# 02_MCU_LCD.net
KiCad netlist of a schematic drawn in Altium Designer
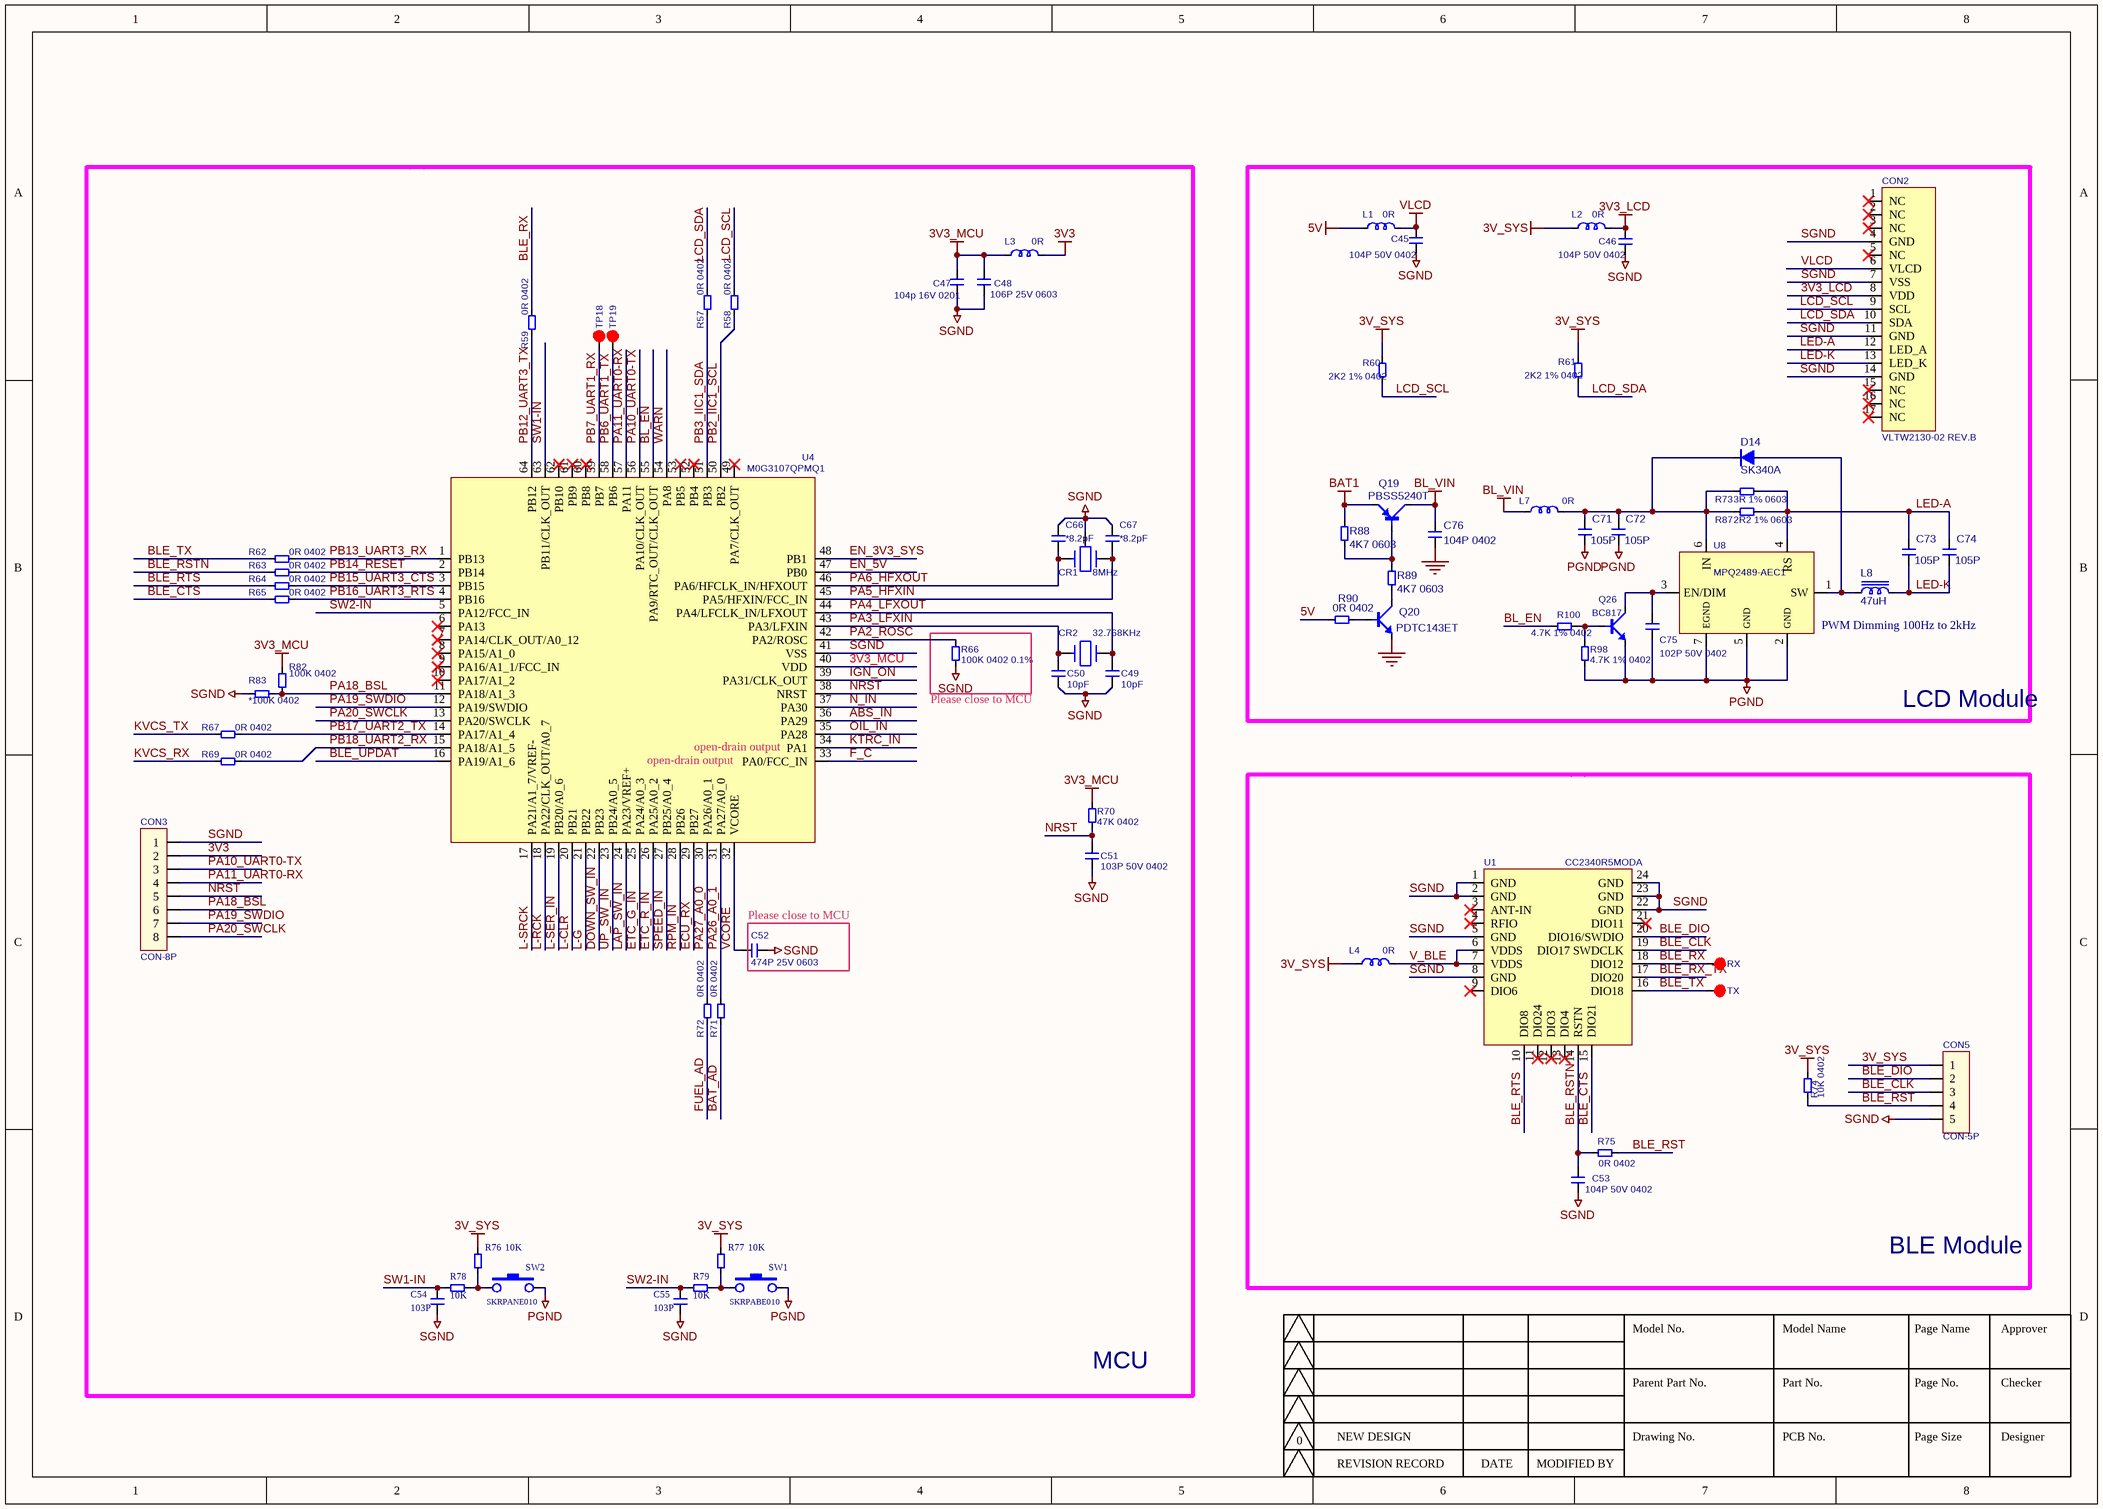
[diagram p0: 02_MCU_LCD.SchDoc]

(export (version "E")
  (design (tool "Eeschema 10.0.6"))
  (components
    (comp (ref "C45")
      (value "104P 50V 0402")
      (footprint "C0402")
      (description "Capacitor")
      (libsource (lib "CTE") (part "C"))
    )
    (comp (ref "C46")
      (value "104P 50V 0402")
      (footprint "C0402")
      (description "Capacitor")
      (libsource (lib "CTE") (part "C"))
    )
    (comp (ref "C47")
      (value "104p 16V 0201")
      (footprint "C0201")
      (description "Capacitor")
      (libsource (lib "CTE") (part "C"))
    )
    (comp (ref "C48")
      (value "106P 25V 0603")
      (footprint "C0603")
      (description "Capacitor")
      (libsource (lib "CTE") (part "C"))
    )
    (comp (ref "C49")
      (value "10pF")
      (footprint "C0402")
      (description "Capacitor")
      (libsource (lib "CTE") (part "C"))
    )
    (comp (ref "C50")
      (value "10pF")
      (footprint "C0402")
      (description "Capacitor")
      (libsource (lib "CTE") (part "C"))
    )
    (comp (ref "C51")
      (value "103P 50V 0402")
      (footprint "C0402")
      (description "Capacitor")
      (libsource (lib "CTE") (part "C"))
    )
    (comp (ref "C52")
      (value "474P 25V 0603")
      (footprint "C0603")
      (description "Capacitor")
      (libsource (lib "CTE") (part "C"))
    )
    (comp (ref "C53")
      (value "104P 50V 0402")
      (footprint "C0402")
      (description "Capacitor")
      (libsource (lib "CTE") (part "C"))
    )
    (comp (ref "C54")
      (value "103P")
      (footprint "C0402")
      (description "Capacitor")
      (libsource (lib "CTE") (part "C"))
    )
    (comp (ref "C55")
      (value "103P")
      (footprint "C0402")
      (description "Capacitor")
      (libsource (lib "CTE") (part "C"))
    )
    (comp (ref "C66")
      (value "*8.2pF")
      (footprint "C0402")
      (description "Capacitor")
      (libsource (lib "CTE") (part "C"))
    )
    (comp (ref "C67")
      (value "*8.2pF")
      (footprint "C0402")
      (description "Capacitor")
      (libsource (lib "CTE") (part "C"))
    )
    (comp (ref "C71")
      (value "105P")
      (footprint "C0603")
      (description "Capacitor")
      (libsource (lib "CTE") (part "C"))
    )
    (comp (ref "C72")
      (value "105P")
      (footprint "C0603")
      (description "Capacitor")
      (libsource (lib "CTE") (part "C"))
    )
    (comp (ref "C73")
      (value "105P")
      (footprint "C0603")
      (description "Capacitor")
      (libsource (lib "CTE") (part "C"))
    )
    (comp (ref "C74")
      (value "105P")
      (footprint "C0603")
      (description "Capacitor")
      (libsource (lib "CTE") (part "C"))
    )
    (comp (ref "C75")
      (value "102P 50V 0402")
      (footprint "C0402")
      (description "Capacitor")
      (libsource (lib "CTE") (part "C"))
    )
    (comp (ref "C76")
      (value "104P 0402")
      (footprint "c0402")
      (description "Capacitor")
      (libsource (lib "CTE") (part "C"))
    )
    (comp (ref "CON2")
      (value "VLTW2130-02 REV.B")
      (footprint "FPC-BL112-17P")
      (libsource (lib "Schlib1") (part "VLTW2130-02 REV.B"))
    )
    (comp (ref "CON3")
      (value "CON-8P")
      (footprint "CON-2.0(9021-N)-8P")
      (libsource (lib "CTE") (part "CON-8P"))
    )
    (comp (ref "CON5") (value "CON-5P") (footprint "CON-2.0V-5P") (libsource (lib "CTE") (part "CON-5P")))
    (comp (ref "CR1")
      (value "8MHz")
      (footprint "CR-3CE")
      (description "Crystal")
      (libsource (lib "CTE") (part "CR-1"))
    )
    (comp (ref "CR2")
      (value "32.768KHz")
      (footprint "CR-FC-13A")
      (description "Crystal")
      (libsource (lib "CTE") (part "CR-2"))
    )
    (comp (ref "D14")
      (value "SK340A")
      (footprint "D-SMA")
      (description "BAS16/RR264/1N4148/FM4004/SS14/SSL14/V15PL50")
      (libsource (lib "*") (part "D-SMD"))
    )
    (comp (ref "L1")
      (value "0R")
      (footprint "0603")
      (description "BEAD101")
      (libsource (lib "CTE") (part "L"))
    )
    (comp (ref "L2")
      (value "0R")
      (footprint "0603")
      (description "BEAD101")
      (libsource (lib "CTE") (part "L"))
    )
    (comp (ref "L3")
      (value "0R")
      (footprint "0603")
      (description "BEAD101")
      (libsource (lib "CTE") (part "L"))
    )
    (comp (ref "L4")
      (value "0R")
      (footprint "0603")
      (description "BEAD101")
      (libsource (lib "CTE") (part "L"))
    )
    (comp (ref "L7")
      (value "0R")
      (footprint "0603")
      (description "BEAD101")
      (libsource (lib "CTE") (part "L"))
    )
    (comp (ref "L8") (value "47uH") (footprint "L-7.4X6.8") (libsource (lib "*") (part "L-1")))
    (comp (ref "Q19")
      (value "PBSS5240T")
      (footprint "SOT23-RF")
      (description "BC807，2SA1812，PBSS9110T")
      (libsource (lib "CTE") (part "Q-PNP(BCE)"))
    )
    (comp (ref "Q20")
      (value "PDTC143ET")
      (footprint "SOT23-RF")
      (description "BC817，PDTC143ET，2SD2211，2SD1918")
      (libsource (lib "CTE") (part "Q-NPN(BCE)"))
    )
    (comp (ref "Q26")
      (value "BC817")
      (footprint "SOT323")
      (description "BC817，PDTC143ET，2SD2211，2SD1918")
      (libsource (lib "CTE") (part "Q-NPN(BCE)"))
    )
    (comp (ref "R57") (value "0R 0402") (footprint "0402") (libsource (lib "CTE") (part "R")))
    (comp (ref "R58") (value "0R 0402") (footprint "0402") (libsource (lib "CTE") (part "R")))
    (comp (ref "R59") (value "0R 0402") (footprint "0402") (libsource (lib "CTE") (part "R")))
    (comp (ref "R60") (value "2K2 1% 0402") (footprint "0402") (libsource (lib "CTE") (part "R")))
    (comp (ref "R61") (value "2K2 1% 0402") (footprint "0402") (libsource (lib "CTE") (part "R")))
    (comp (ref "R62") (value "0R 0402") (footprint "0402") (libsource (lib "CTE") (part "R")))
    (comp (ref "R63")
      (value "0R 0402")
      (footprint "0402")
      (description "0603")
      (libsource (lib "PADS") (part "R-0603"))
    )
    (comp (ref "R64") (value "0R 0402") (footprint "0402") (libsource (lib "CTE") (part "R")))
    (comp (ref "R65") (value "0R 0402") (footprint "0402") (libsource (lib "CTE") (part "R")))
    (comp (ref "R66")
      (value "100K 0402 0.1%")
      (footprint "0402")
      (description "0603")
      (libsource (lib "PADS") (part "R-0603"))
    )
    (comp (ref "R67") (value "0R 0402") (footprint "0402") (libsource (lib "CTE") (part "R")))
    (comp (ref "R69") (value "0R 0402") (footprint "0402") (libsource (lib "CTE") (part "R")))
    (comp (ref "R70")
      (value "47K 0402")
      (footprint "0402")
      (description "0603")
      (libsource (lib "PADS") (part "R-0603"))
    )
    (comp (ref "R71") (value "0R 0402") (footprint "0402") (libsource (lib "CTE") (part "R")))
    (comp (ref "R72") (value "0R 0402") (footprint "0402") (libsource (lib "CTE") (part "R")))
    (comp (ref "R73") (value "3R 1% 0603") (footprint "0603") (libsource (lib "CTE") (part "R")))
    (comp (ref "R74")
      (value "10K 0402")
      (footprint "0402")
      (description "0603")
      (libsource (lib "PADS") (part "R-0603"))
    )
    (comp (ref "R75")
      (value "0R 0402")
      (footprint "0402")
      (description "0603")
      (libsource (lib "PADS") (part "R-0603"))
    )
    (comp (ref "R76")
      (value "10K")
      (footprint "0402")
      (description "0603")
      (libsource (lib "CTE") (part "R-0603"))
    )
    (comp (ref "R77")
      (value "10K")
      (footprint "0402")
      (description "0603")
      (libsource (lib "CTE") (part "R-0603"))
    )
    (comp (ref "R78")
      (value "10K")
      (footprint "0402")
      (description "0603")
      (libsource (lib "CTE") (part "R-0603"))
    )
    (comp (ref "R79")
      (value "10K")
      (footprint "0402")
      (description "0603")
      (libsource (lib "CTE") (part "R-0603"))
    )
    (comp (ref "R82")
      (value "100K 0402")
      (footprint "0402")
      (description "0603")
      (libsource (lib "PADS") (part "R-0603"))
    )
    (comp (ref "R83")
      (value "*100K 0402")
      (footprint "0402")
      (description "0603")
      (libsource (lib "PADS") (part "R-0603"))
    )
    (comp (ref "R87") (value "2R2 1% 0603") (footprint "0603") (libsource (lib "CTE") (part "R")))
    (comp (ref "R88") (value "4K7 0603") (footprint "0603") (libsource (lib "CTE") (part "R")))
    (comp (ref "R89") (value "4K7 0603") (footprint "0603") (libsource (lib "CTE") (part "R")))
    (comp (ref "R90")
      (value "0R 0402")
      (footprint "0402")
      (description "0603")
      (libsource (lib "PADS") (part "R-0603"))
    )
    (comp (ref "R98") (value "4.7K 1% 0402") (footprint "0402") (libsource (lib "CTE") (part "R")))
    (comp (ref "R100") (value "4.7K 1% 0402") (footprint "0402") (libsource (lib "CTE") (part "R")))
    (comp (ref "RX") (value "TEST") (footprint "TEST") (libsource (lib "CTE") (part "TEST")))
    (comp (ref "SW1") (value "SKRPABE010") (footprint "SW-SKRPABE010") (libsource (lib "CTE") (part "SW-PB")))
    (comp (ref "SW2") (value "SKRPANE010") (footprint "SW-SKRPABE010") (libsource (lib "CTE") (part "SW-PB")))
    (comp (ref "TP18") (value "TEST") (footprint "TEST") (libsource (lib "CTE") (part "TEST")))
    (comp (ref "TP19") (value "TEST") (footprint "TEST") (libsource (lib "CTE") (part "TEST")))
    (comp (ref "TX") (value "TEST") (footprint "TEST") (libsource (lib "CTE") (part "TEST")))
    (comp (ref "U1")
      (value "CC2340R5MODA")
      (footprint "IC-MOD-CC2340R5")
      (libsource (lib "Schlib1") (part "CC234055MODA"))
    )
    (comp (ref "U4")
      (value "M0G3107QPMQ1")
      (footprint "IC-M0G3107-64")
      (libsource (lib "Schlib1") (part "M0G3107QPMQ1"))
    )
    (comp (ref "U8")
      (value "MPQ2489-AEC1")
      (footprint "IC-QFN6-3X3")
      (libsource (lib "Schlib1") (part "MPQ2489-AEC1"))
    )
  )
  (nets
    (net (code "1") (name "/ABS_IN") (class "Default")
      (node (ref "U4") (pin "36") (pinfunction "PA29_36") (pintype "passive"))
    )
    (net (code "2") (name "/BAT_AD") (class "Default")
      (node (ref "R71") (pin "2") (pinfunction "2_2") (pintype "passive"))
    )
    (net (code "3") (name "/BLE_CLK") (class "Default")
      (node (ref "CON5") (pin "3") (pinfunction "3_3") (pintype "passive"))
      (node (ref "U1") (pin "19") (pinfunction "DIO17_SWDCLK_19") (pintype "passive"))
    )
    (net (code "4") (name "/BLE_CTS") (class "Default")
      (node (ref "R65") (pin "2") (pinfunction "2_2") (pintype "passive"))
      (node (ref "U1") (pin "15") (pinfunction "DIO21_15") (pintype "passive"))
    )
    (net (code "5") (name "/BLE_DIO") (class "Default")
      (node (ref "CON5") (pin "2") (pinfunction "2_2") (pintype "passive"))
      (node (ref "U1") (pin "20") (pinfunction "DIO16/SWDIO_20") (pintype "passive"))
    )
    (net (code "6") (name "/BLE_RST") (class "Default")
      (node (ref "CON5") (pin "4") (pinfunction "4_4") (pintype "passive"))
      (node (ref "R74") (pin "1") (pinfunction "1_1") (pintype "passive"))
      (node (ref "R75") (pin "2") (pinfunction "2_2") (pintype "passive"))
    )
    (net (code "7") (name "/BLE_RSTN") (class "Default")
      (node (ref "C53") (pin "1") (pinfunction "1_1") (pintype "passive"))
      (node (ref "R63") (pin "1") (pinfunction "1_1") (pintype "passive"))
      (node (ref "R75") (pin "1") (pinfunction "1_1") (pintype "passive"))
      (node (ref "U1") (pin "14") (pinfunction "RSTN_14") (pintype "passive"))
    )
    (net (code "8") (name "/BLE_RTS") (class "Default")
      (node (ref "R64") (pin "2") (pinfunction "2_2") (pintype "passive"))
      (node (ref "U1") (pin "10") (pinfunction "DIO8_10") (pintype "passive"))
    )
    (net (code "9") (name "/BLE_RX") (class "Default")
      (node (ref "R59") (pin "1") (pinfunction "1_1") (pintype "passive"))
      (node (ref "RX") (pin "TP") (pinfunction "TP_TP") (pintype "passive"))
      (node (ref "U1") (pin "18") (pinfunction "DIO12_18") (pintype "passive"))
    )
    (net (code "10") (name "/BLE_RX_TX") (class "Default")
      (node (ref "U1") (pin "17") (pinfunction "DIO20_17") (pintype "passive"))
    )
    (net (code "11") (name "/BLE_TX") (class "Default")
      (node (ref "R62") (pin "2") (pinfunction "2_2") (pintype "passive"))
      (node (ref "TX") (pin "TP") (pinfunction "TP_TP") (pintype "passive"))
      (node (ref "U1") (pin "16") (pinfunction "DIO18_16") (pintype "passive"))
    )
    (net (code "12") (name "/BLE_UPDAT") (class "Default")
      (node (ref "U4") (pin "16") (pinfunction "PA19/A1_6_16") (pintype "passive"))
    )
    (net (code "13") (name "/BL_EN") (class "Default")
      (node (ref "R100") (pin "2") (pinfunction "2_2") (pintype "passive"))
      (node (ref "U4") (pin "55") (pinfunction "PA9/RTC_OUT/CLK_OUT_55") (pintype "passive"))
    )
    (net (code "14") (name "/DOWN_SW_IN") (class "Default")
      (node (ref "U4") (pin "22") (pinfunction "PB23_22") (pintype "passive"))
    )
    (net (code "15") (name "/ECU_RX") (class "Default")
      (node (ref "U4") (pin "29") (pinfunction "PB27_29") (pintype "passive"))
    )
    (net (code "16") (name "/EN_3V3_SYS") (class "Default")
      (node (ref "U4") (pin "48") (pinfunction "PB1_48") (pintype "passive"))
    )
    (net (code "17") (name "/EN_5V") (class "Default")
      (node (ref "U4") (pin "47") (pinfunction "PB0_47") (pintype "passive"))
    )
    (net (code "18") (name "/ETC_G_IN") (class "Default")
      (node (ref "U4") (pin "25") (pinfunction "PA24/A0_3_25") (pintype "passive"))
    )
    (net (code "19") (name "/ETC_R_IN") (class "Default")
      (node (ref "U4") (pin "26") (pinfunction "PA25/A0_2_26") (pintype "passive"))
    )
    (net (code "20") (name "/FUEL_AD") (class "Default")
      (node (ref "R72") (pin "2") (pinfunction "2_2") (pintype "passive"))
    )
    (net (code "21") (name "/F_C") (class "Default")
      (node (ref "U4") (pin "33") (pinfunction "PA0/FCC_IN_33") (pintype "passive"))
    )
    (net (code "22") (name "/IGN_ON") (class "Default")
      (node (ref "U4") (pin "39") (pinfunction "PA31/CLK_OUT_39") (pintype "passive"))
    )
    (net (code "23") (name "/KTRC_IN") (class "Default")
      (node (ref "U4") (pin "34") (pinfunction "PA1_34") (pintype "passive"))
    )
    (net (code "24") (name "/KVCS_RX") (class "Default")
      (node (ref "R69") (pin "1") (pinfunction "1_1") (pintype "passive"))
    )
    (net (code "25") (name "/KVCS_TX") (class "Default")
      (node (ref "R67") (pin "1") (pinfunction "1_1") (pintype "passive"))
    )
    (net (code "26") (name "/L-CLR") (class "Default")
      (node (ref "U4") (pin "20") (pinfunction "PB21_20") (pintype "passive"))
    )
    (net (code "27") (name "/L-G") (class "Default")
      (node (ref "U4") (pin "21") (pinfunction "PB22_21") (pintype "passive"))
    )
    (net (code "28") (name "/L-RCK") (class "Default")
      (node (ref "U4") (pin "18") (pinfunction "PA22/CLK_OUT/A0_7_18") (pintype "passive"))
    )
    (net (code "29") (name "/L-SER_IN") (class "Default")
      (node (ref "U4") (pin "19") (pinfunction "PB20/A0_6_19") (pintype "passive"))
    )
    (net (code "30") (name "/L-SRCK") (class "Default")
      (node (ref "U4") (pin "17") (pinfunction "PA21/A1_7/VREF-_17") (pintype "passive"))
    )
    (net (code "31") (name "/LAP_SW_IN") (class "Default")
      (node (ref "U4") (pin "24") (pinfunction "PA23/VREF+_24") (pintype "passive"))
    )
    (net (code "32") (name "/LCD_SCL") (class "Default")
      (node (ref "CON2") (pin "9") (pinfunction "SCL_9") (pintype "passive"))
      (node (ref "R58") (pin "2") (pinfunction "2_2") (pintype "passive"))
      (node (ref "R60") (pin "1") (pinfunction "1_1") (pintype "passive"))
    )
    (net (code "33") (name "/LCD_SDA") (class "Default")
      (node (ref "CON2") (pin "10") (pinfunction "SDA_10") (pintype "passive"))
      (node (ref "R57") (pin "2") (pinfunction "2_2") (pintype "passive"))
      (node (ref "R61") (pin "1") (pinfunction "1_1") (pintype "passive"))
    )
    (net (code "34") (name "/LED-A") (class "Default")
      (node (ref "C73") (pin "1") (pinfunction "1_1") (pintype "passive"))
      (node (ref "C74") (pin "1") (pinfunction "1_1") (pintype "passive"))
      (node (ref "CON2") (pin "12") (pinfunction "LED_A_12") (pintype "passive"))
      (node (ref "R73") (pin "1") (pinfunction "1_1") (pintype "passive"))
      (node (ref "R87") (pin "1") (pinfunction "1_1") (pintype "passive"))
      (node (ref "U8") (pin "4") (pinfunction "RS_4") (pintype "passive"))
    )
    (net (code "35") (name "/LED-K") (class "Default")
      (node (ref "C73") (pin "2") (pinfunction "2_2") (pintype "passive"))
      (node (ref "C74") (pin "2") (pinfunction "2_2") (pintype "passive"))
      (node (ref "CON2") (pin "13") (pinfunction "LED_K_13") (pintype "passive"))
      (node (ref "L8") (pin "2") (pinfunction "2_2") (pintype "passive"))
    )
    (net (code "36") (name "/NRST") (class "Default")
      (node (ref "C51") (pin "1") (pinfunction "1_1") (pintype "passive"))
      (node (ref "CON3") (pin "5") (pinfunction "5_5") (pintype "passive"))
      (node (ref "R70") (pin "2") (pinfunction "2_2") (pintype "passive"))
      (node (ref "U4") (pin "38") (pinfunction "NRST_38") (pintype "passive"))
    )
    (net (code "37") (name "/N_IN") (class "Default")
      (node (ref "U4") (pin "37") (pinfunction "PA30_37") (pintype "passive"))
    )
    (net (code "38") (name "/OIL_IN") (class "Default")
      (node (ref "U4") (pin "35") (pinfunction "PA28_35") (pintype "passive"))
    )
    (net (code "39") (name "/PA2_ROSC") (class "Default")
      (node (ref "R66") (pin "1") (pinfunction "1_1") (pintype "passive"))
      (node (ref "U4") (pin "42") (pinfunction "PA2/ROSC_42") (pintype "passive"))
    )
    (net (code "40") (name "/PA3_LFXIN") (class "Default")
      (node (ref "C50") (pin "1") (pinfunction "1_1") (pintype "passive"))
      (node (ref "CR2") (pin "2") (pinfunction "2_2") (pintype "passive"))
      (node (ref "U4") (pin "43") (pinfunction "PA3/LFXIN_43") (pintype "passive"))
    )
    (net (code "41") (name "/PA4_LFXOUT") (class "Default")
      (node (ref "C49") (pin "1") (pinfunction "1_1") (pintype "passive"))
      (node (ref "CR2") (pin "1") (pinfunction "1_1") (pintype "passive"))
      (node (ref "U4") (pin "44") (pinfunction "PA4/LFCLK_IN/LFXOUT_44") (pintype "passive"))
    )
    (net (code "42") (name "/PA5_HFXIN") (class "Default")
      (node (ref "C67") (pin "1") (pinfunction "1_1") (pintype "passive"))
      (node (ref "CR1") (pin "2") (pinfunction "2_2") (pintype "passive"))
      (node (ref "U4") (pin "45") (pinfunction "PA5/HFXIN/FCC_IN_45") (pintype "passive"))
    )
    (net (code "43") (name "/PA6_HFXOUT") (class "Default")
      (node (ref "C66") (pin "1") (pinfunction "1_1") (pintype "passive"))
      (node (ref "CR1") (pin "1") (pinfunction "1_1") (pintype "passive"))
      (node (ref "U4") (pin "46") (pinfunction "PA6/HFCLK_IN/HFXOUT_46") (pintype "passive"))
    )
    (net (code "44") (name "/PA10_UART0-TX") (class "Default")
      (node (ref "CON3") (pin "3") (pinfunction "3_3") (pintype "passive"))
      (node (ref "U4") (pin "56") (pinfunction "PA10/CLK_OUT_56") (pintype "passive"))
    )
    (net (code "45") (name "/PA11_UART0-RX") (class "Default")
      (node (ref "CON3") (pin "4") (pinfunction "4_4") (pintype "passive"))
      (node (ref "U4") (pin "57") (pinfunction "PA11_57") (pintype "passive"))
    )
    (net (code "46") (name "/PA18_BSL") (class "Default")
      (node (ref "CON3") (pin "6") (pinfunction "6_6") (pintype "passive"))
      (node (ref "R82") (pin "2") (pinfunction "2_2") (pintype "passive"))
      (node (ref "R83") (pin "1") (pinfunction "1_1") (pintype "passive"))
      (node (ref "U4") (pin "11") (pinfunction "PA18/A1_3_11") (pintype "passive"))
    )
    (net (code "47") (name "/PA19_SWDIO") (class "Default")
      (node (ref "CON3") (pin "7") (pinfunction "7_7") (pintype "passive"))
      (node (ref "U4") (pin "12") (pinfunction "PA19/SWDIO_12") (pintype "passive"))
    )
    (net (code "48") (name "/PA20_SWCLK") (class "Default")
      (node (ref "CON3") (pin "8") (pinfunction "8_8") (pintype "passive"))
      (node (ref "U4") (pin "13") (pinfunction "PA20/SWCLK_13") (pintype "passive"))
    )
    (net (code "49") (name "/PA26_A0_1") (class "Default")
      (node (ref "R71") (pin "1") (pinfunction "1_1") (pintype "passive"))
      (node (ref "U4") (pin "31") (pinfunction "PA27/A0_0_31") (pintype "passive"))
    )
    (net (code "50") (name "/PA27_A0_0") (class "Default")
      (node (ref "R72") (pin "1") (pinfunction "1_1") (pintype "passive"))
      (node (ref "U4") (pin "30") (pinfunction "PA26/A0_1_30") (pintype "passive"))
    )
    (net (code "51") (name "/PB2_IIC1_SCL") (class "Default")
      (node (ref "R58") (pin "1") (pinfunction "1_1") (pintype "passive"))
      (node (ref "U4") (pin "50") (pinfunction "PB2_50") (pintype "passive"))
    )
    (net (code "52") (name "/PB3_IIC1_SDA") (class "Default")
      (node (ref "R57") (pin "1") (pinfunction "1_1") (pintype "passive"))
      (node (ref "U4") (pin "51") (pinfunction "PB3_51") (pintype "passive"))
    )
    (net (code "53") (name "/PB6_UART1_TX") (class "Default")
      (node (ref "TP19") (pin "TP") (pinfunction "TP_TP") (pintype "passive"))
      (node (ref "U4") (pin "58") (pinfunction "PB6_58") (pintype "passive"))
    )
    (net (code "54") (name "/PB7_UART1_RX") (class "Default")
      (node (ref "TP18") (pin "TP") (pinfunction "TP_TP") (pintype "passive"))
      (node (ref "U4") (pin "59") (pinfunction "PB7_59") (pintype "passive"))
    )
    (net (code "55") (name "/PB12_UART3_TX") (class "Default")
      (node (ref "R59") (pin "2") (pinfunction "2_2") (pintype "passive"))
      (node (ref "U4") (pin "64") (pinfunction "PB12_64") (pintype "passive"))
    )
    (net (code "56") (name "/PB13_UART3_RX") (class "Default")
      (node (ref "R62") (pin "1") (pinfunction "1_1") (pintype "passive"))
      (node (ref "U4") (pin "1") (pinfunction "PB13_1") (pintype "passive"))
    )
    (net (code "57") (name "/PB14_RESET") (class "Default")
      (node (ref "R63") (pin "2") (pinfunction "2_2") (pintype "passive"))
      (node (ref "U4") (pin "2") (pinfunction "PB14_2") (pintype "passive"))
    )
    (net (code "58") (name "/PB15_UART3_CTS") (class "Default")
      (node (ref "R64") (pin "1") (pinfunction "1_1") (pintype "passive"))
      (node (ref "U4") (pin "3") (pinfunction "PB15_3") (pintype "passive"))
    )
    (net (code "59") (name "/PB16_UART3_RTS") (class "Default")
      (node (ref "R65") (pin "1") (pinfunction "1_1") (pintype "passive"))
      (node (ref "U4") (pin "4") (pinfunction "PB16_4") (pintype "passive"))
    )
    (net (code "60") (name "/PB17_UART2_TX") (class "Default")
      (node (ref "R67") (pin "2") (pinfunction "2_2") (pintype "passive"))
      (node (ref "U4") (pin "14") (pinfunction "PA17/A1_4_14") (pintype "passive"))
    )
    (net (code "61") (name "/PB18_UART2_RX") (class "Default")
      (node (ref "R69") (pin "2") (pinfunction "2_2") (pintype "passive"))
      (node (ref "U4") (pin "15") (pinfunction "PA18/A1_5_15") (pintype "passive"))
    )
    (net (code "62") (name "/RPM_IN") (class "Default")
      (node (ref "U4") (pin "28") (pinfunction "PB26_28") (pintype "passive"))
    )
    (net (code "63") (name "/SPEED_IN") (class "Default")
      (node (ref "U4") (pin "27") (pinfunction "PB25/A0_4_27") (pintype "passive"))
    )
    (net (code "64") (name "/SW1-IN") (class "Default")
      (node (ref "C54") (pin "1") (pinfunction "1_1") (pintype "passive"))
      (node (ref "R78") (pin "2") (pinfunction "2_2") (pintype "passive"))
      (node (ref "U4") (pin "63") (pinfunction "PB11/CLK_OUT_63") (pintype "passive"))
    )
    (net (code "65") (name "/SW2-IN") (class "Default")
      (node (ref "C55") (pin "1") (pinfunction "1_1") (pintype "passive"))
      (node (ref "R79") (pin "2") (pinfunction "2_2") (pintype "passive"))
      (node (ref "U4") (pin "5") (pinfunction "PA12/FCC_IN_5") (pintype "passive"))
    )
    (net (code "66") (name "/UP_SW_IN") (class "Default")
      (node (ref "U4") (pin "23") (pinfunction "PB24/A0_5_23") (pintype "passive"))
    )
    (net (code "67") (name "/VCORE") (class "Default")
      (node (ref "C52") (pin "1") (pinfunction "1_1") (pintype "passive"))
      (node (ref "U4") (pin "32") (pinfunction "VCORE_32") (pintype "passive"))
    )
    (net (code "68") (name "/V_BLE") (class "Default")
      (node (ref "L4") (pin "2") (pinfunction "2_2") (pintype "passive"))
      (node (ref "U1") (pin "6") (pinfunction "VDDS_6") (pintype "passive"))
      (node (ref "U1") (pin "7") (pinfunction "VDDS_7") (pintype "passive"))
    )
    (net (code "69") (name "/WARN") (class "Default")
      (node (ref "U4") (pin "54") (pinfunction "PA8_54") (pintype "passive"))
    )
    (net (code "70") (name "3V3") (class "Default")
      (node (ref "CON3") (pin "2") (pinfunction "2_2") (pintype "passive"))
      (node (ref "L3") (pin "2") (pinfunction "2_2") (pintype "passive"))
    )
    (net (code "71") (name "3V3_LCD") (class "Default")
      (node (ref "C46") (pin "1") (pinfunction "1_1") (pintype "passive"))
      (node (ref "CON2") (pin "8") (pinfunction "VDD_8") (pintype "passive"))
      (node (ref "L2") (pin "2") (pinfunction "2_2") (pintype "passive"))
    )
    (net (code "72") (name "3V3_MCU") (class "Default")
      (node (ref "C47") (pin "1") (pinfunction "1_1") (pintype "passive"))
      (node (ref "C48") (pin "1") (pinfunction "1_1") (pintype "passive"))
      (node (ref "L3") (pin "1") (pinfunction "1_1") (pintype "passive"))
      (node (ref "R70") (pin "1") (pinfunction "1_1") (pintype "passive"))
      (node (ref "R82") (pin "1") (pinfunction "1_1") (pintype "passive"))
      (node (ref "U4") (pin "40") (pinfunction "VDD_40") (pintype "passive"))
    )
    (net (code "73") (name "3V_SYS") (class "Default")
      (node (ref "CON5") (pin "1") (pinfunction "1_1") (pintype "passive"))
      (node (ref "L2") (pin "1") (pinfunction "1_1") (pintype "passive"))
      (node (ref "L4") (pin "1") (pinfunction "1_1") (pintype "passive"))
      (node (ref "R60") (pin "2") (pinfunction "2_2") (pintype "passive"))
      (node (ref "R61") (pin "2") (pinfunction "2_2") (pintype "passive"))
      (node (ref "R74") (pin "2") (pinfunction "2_2") (pintype "passive"))
      (node (ref "R76") (pin "2") (pinfunction "2_2") (pintype "passive"))
      (node (ref "R77") (pin "2") (pinfunction "2_2") (pintype "passive"))
    )
    (net (code "74") (name "5V") (class "Default")
      (node (ref "L1") (pin "1") (pinfunction "1_1") (pintype "passive"))
      (node (ref "R90") (pin "1") (pinfunction "1_1") (pintype "passive"))
    )
    (net (code "75") (name "BAT1") (class "Default")
      (node (ref "Q19") (pin "3") (pinfunction "E_3") (pintype "passive"))
      (node (ref "R88") (pin "1") (pinfunction "1_1") (pintype "passive"))
    )
    (net (code "76") (name "BL_VIN") (class "Default")
      (node (ref "C76") (pin "1") (pinfunction "1_1") (pintype "passive"))
      (node (ref "L7") (pin "1") (pinfunction "1_1") (pintype "passive"))
      (node (ref "Q19") (pin "2") (pinfunction "C_2") (pintype "passive"))
    )
    (net (code "77") (name "GND") (class "Default")
      (node (ref "C76") (pin "2") (pinfunction "2_2") (pintype "passive"))
      (node (ref "Q20") (pin "3") (pinfunction "E_3") (pintype "passive"))
    )
    (net (code "78") (name "Net-(D14-A)") (class "Default")
      (node (ref "D14") (pin "1") (pinfunction "A_1") (pintype "passive"))
      (node (ref "L8") (pin "1") (pinfunction "1_1") (pintype "passive"))
      (node (ref "U8") (pin "1") (pinfunction "SW_1") (pintype "passive"))
    )
    (net (code "79") (name "Net-(D14-K)") (class "Default")
      (node (ref "C71") (pin "1") (pinfunction "1_1") (pintype "passive"))
      (node (ref "C72") (pin "1") (pinfunction "1_1") (pintype "passive"))
      (node (ref "D14") (pin "2") (pinfunction "K_2") (pintype "passive"))
      (node (ref "L7") (pin "2") (pinfunction "2_2") (pintype "passive"))
      (node (ref "R73") (pin "2") (pinfunction "2_2") (pintype "passive"))
      (node (ref "R87") (pin "2") (pinfunction "2_2") (pintype "passive"))
      (node (ref "U8") (pin "6") (pinfunction "IN_6") (pintype "passive"))
    )
    (net (code "80") (name "Net-(Q19-B)") (class "Default")
      (node (ref "Q19") (pin "1") (pinfunction "B_1") (pintype "passive"))
      (node (ref "R88") (pin "2") (pinfunction "2_2") (pintype "passive"))
      (node (ref "R89") (pin "1") (pinfunction "1_1") (pintype "passive"))
    )
    (net (code "81") (name "Net-(Q20-B)") (class "Default")
      (node (ref "Q20") (pin "1") (pinfunction "B_1") (pintype "passive"))
      (node (ref "R90") (pin "2") (pinfunction "2_2") (pintype "passive"))
    )
    (net (code "82") (name "Net-(Q20-C)") (class "Default")
      (node (ref "Q20") (pin "2") (pinfunction "C_2") (pintype "passive"))
      (node (ref "R89") (pin "2") (pinfunction "2_2") (pintype "passive"))
    )
    (net (code "83") (name "Net-(Q26-B)") (class "Default")
      (node (ref "Q26") (pin "1") (pinfunction "B_1") (pintype "passive"))
      (node (ref "R100") (pin "1") (pinfunction "1_1") (pintype "passive"))
      (node (ref "R98") (pin "1") (pinfunction "1_1") (pintype "passive"))
    )
    (net (code "84") (name "Net-(Q26-C)") (class "Default")
      (node (ref "C75") (pin "2") (pinfunction "2_2") (pintype "passive"))
      (node (ref "Q26") (pin "2") (pinfunction "C_2") (pintype "passive"))
      (node (ref "U8") (pin "3") (pinfunction "EN/DIM_3") (pintype "passive"))
    )
    (net (code "85") (name "Net-(R76-Pad1)") (class "Default")
      (node (ref "R76") (pin "1") (pinfunction "1_1") (pintype "passive"))
      (node (ref "R78") (pin "1") (pinfunction "1_1") (pintype "passive"))
      (node (ref "SW2") (pin "1") (pinfunction "1_1") (pintype "passive"))
    )
    (net (code "86") (name "Net-(R77-Pad1)") (class "Default")
      (node (ref "R77") (pin "1") (pinfunction "1_1") (pintype "passive"))
      (node (ref "R79") (pin "1") (pinfunction "1_1") (pintype "passive"))
      (node (ref "SW1") (pin "1") (pinfunction "1_1") (pintype "passive"))
    )
    (net (code "87") (name "PGND") (class "Default")
      (node (ref "C71") (pin "2") (pinfunction "2_2") (pintype "passive"))
      (node (ref "C72") (pin "2") (pinfunction "2_2") (pintype "passive"))
      (node (ref "C75") (pin "1") (pinfunction "1_1") (pintype "passive"))
      (node (ref "Q26") (pin "3") (pinfunction "E_3") (pintype "passive"))
      (node (ref "R98") (pin "2") (pinfunction "2_2") (pintype "passive"))
      (node (ref "SW1") (pin "2") (pinfunction "2_2") (pintype "passive"))
      (node (ref "SW2") (pin "2") (pinfunction "2_2") (pintype "passive"))
      (node (ref "U8") (pin "2") (pinfunction "GND_2") (pintype "passive"))
      (node (ref "U8") (pin "5") (pinfunction "GND_5") (pintype "passive"))
      (node (ref "U8") (pin "7") (pinfunction "EGND_7") (pintype "passive"))
    )
    (net (code "88") (name "SGND") (class "Default")
      (node (ref "C45") (pin "2") (pinfunction "2_2") (pintype "passive"))
      (node (ref "C46") (pin "2") (pinfunction "2_2") (pintype "passive"))
      (node (ref "C47") (pin "2") (pinfunction "2_2") (pintype "passive"))
      (node (ref "C48") (pin "2") (pinfunction "2_2") (pintype "passive"))
      (node (ref "C49") (pin "2") (pinfunction "2_2") (pintype "passive"))
      (node (ref "C50") (pin "2") (pinfunction "2_2") (pintype "passive"))
      (node (ref "C51") (pin "2") (pinfunction "2_2") (pintype "passive"))
      (node (ref "C52") (pin "2") (pinfunction "2_2") (pintype "passive"))
      (node (ref "C53") (pin "2") (pinfunction "2_2") (pintype "passive"))
      (node (ref "C54") (pin "2") (pinfunction "2_2") (pintype "passive"))
      (node (ref "C55") (pin "2") (pinfunction "2_2") (pintype "passive"))
      (node (ref "C66") (pin "2") (pinfunction "2_2") (pintype "passive"))
      (node (ref "C67") (pin "2") (pinfunction "2_2") (pintype "passive"))
      (node (ref "CON2") (pin "11") (pinfunction "GND_11") (pintype "passive"))
      (node (ref "CON2") (pin "14") (pinfunction "GND_14") (pintype "passive"))
      (node (ref "CON2") (pin "4") (pinfunction "GND_4") (pintype "passive"))
      (node (ref "CON2") (pin "7") (pinfunction "VSS_7") (pintype "passive"))
      (node (ref "CON3") (pin "1") (pinfunction "1_1") (pintype "passive"))
      (node (ref "CON5") (pin "5") (pinfunction "5_5") (pintype "passive"))
      (node (ref "CR1") (pin "3") (pinfunction "3_3") (pintype "passive"))
      (node (ref "R66") (pin "2") (pinfunction "2_2") (pintype "passive"))
      (node (ref "R83") (pin "2") (pinfunction "2_2") (pintype "passive"))
      (node (ref "U1") (pin "1") (pinfunction "GND_1") (pintype "passive"))
      (node (ref "U1") (pin "2") (pinfunction "GND_2") (pintype "passive"))
      (node (ref "U1") (pin "22") (pinfunction "GND_22") (pintype "passive"))
      (node (ref "U1") (pin "23") (pinfunction "GND_23") (pintype "passive"))
      (node (ref "U1") (pin "24") (pinfunction "GND_24") (pintype "passive"))
      (node (ref "U1") (pin "5") (pinfunction "GND_5") (pintype "passive"))
      (node (ref "U1") (pin "8") (pinfunction "GND_8") (pintype "passive"))
      (node (ref "U4") (pin "41") (pinfunction "VSS_41") (pintype "passive"))
    )
    (net (code "89") (name "VLCD") (class "Default")
      (node (ref "C45") (pin "1") (pinfunction "1_1") (pintype "passive"))
      (node (ref "CON2") (pin "6") (pinfunction "VLCD_6") (pintype "passive"))
      (node (ref "L1") (pin "2") (pinfunction "2_2") (pintype "passive"))
    )
    (net (code "90") (name "unconnected-(CON2-NC-Pad1)") (class "Default")
      (node (ref "CON2") (pin "1") (pinfunction "NC_1") (pintype "passive+no_connect"))
    )
    (net (code "91") (name "unconnected-(CON2-NC-Pad2)") (class "Default")
      (node (ref "CON2") (pin "2") (pinfunction "NC_2") (pintype "passive+no_connect"))
    )
    (net (code "92") (name "unconnected-(CON2-NC-Pad3)") (class "Default")
      (node (ref "CON2") (pin "3") (pinfunction "NC_3") (pintype "passive+no_connect"))
    )
    (net (code "93") (name "unconnected-(CON2-NC-Pad5)") (class "Default")
      (node (ref "CON2") (pin "5") (pinfunction "NC_5") (pintype "passive+no_connect"))
    )
    (net (code "94") (name "unconnected-(CON2-NC-Pad15)") (class "Default")
      (node (ref "CON2") (pin "15") (pinfunction "NC_15") (pintype "passive+no_connect"))
    )
    (net (code "95") (name "unconnected-(CON2-NC-Pad16)") (class "Default")
      (node (ref "CON2") (pin "16") (pinfunction "NC_16") (pintype "passive+no_connect"))
    )
    (net (code "96") (name "unconnected-(CON2-NC-Pad17)") (class "Default")
      (node (ref "CON2") (pin "17") (pinfunction "NC_17") (pintype "passive+no_connect"))
    )
    (net (code "97") (name "unconnected-(U1-ANT-IN-Pad3)") (class "Default")
      (node (ref "U1") (pin "3") (pinfunction "ANT-IN_3") (pintype "passive+no_connect"))
    )
    (net (code "98") (name "unconnected-(U1-DIO3-Pad12)") (class "Default")
      (node (ref "U1") (pin "12") (pinfunction "DIO3_12") (pintype "passive+no_connect"))
    )
    (net (code "99") (name "unconnected-(U1-DIO4-Pad13)") (class "Default")
      (node (ref "U1") (pin "13") (pinfunction "DIO4_13") (pintype "passive+no_connect"))
    )
    (net (code "100") (name "unconnected-(U1-DIO6-Pad9)") (class "Default")
      (node (ref "U1") (pin "9") (pinfunction "DIO6_9") (pintype "passive+no_connect"))
    )
    (net (code "101") (name "unconnected-(U1-DIO11-Pad21)") (class "Default")
      (node (ref "U1") (pin "21") (pinfunction "DIO11_21") (pintype "passive+no_connect"))
    )
    (net (code "102") (name "unconnected-(U1-DIO24-Pad11)") (class "Default")
      (node (ref "U1") (pin "11") (pinfunction "DIO24_11") (pintype "passive+no_connect"))
    )
    (net (code "103") (name "unconnected-(U1-RFIO-Pad4)") (class "Default")
      (node (ref "U1") (pin "4") (pinfunction "RFIO_4") (pintype "passive+no_connect"))
    )
    (net (code "104") (name "unconnected-(U4-PA7{slash}CLK_OUT-Pad49)") (class "Default")
      (node (ref "U4") (pin "49") (pinfunction "PA7/CLK_OUT_49") (pintype "passive+no_connect"))
    )
    (net (code "105") (name "unconnected-(U4-PA13-Pad6)") (class "Default")
      (node (ref "U4") (pin "6") (pinfunction "PA13_6") (pintype "passive+no_connect"))
    )
    (net (code "106") (name "unconnected-(U4-PA14{slash}CLK_OUT{slash}A0_12-Pad7)") (class "Default")
      (node (ref "U4") (pin "7") (pinfunction "PA14/CLK_OUT/A0_12_7") (pintype "passive+no_connect"))
    )
    (net (code "107") (name "unconnected-(U4-PA15{slash}A1_0-Pad8)") (class "Default")
      (node (ref "U4") (pin "8") (pinfunction "PA15/A1_0_8") (pintype "passive+no_connect"))
    )
    (net (code "108") (name "unconnected-(U4-PA16{slash}A1_1{slash}FCC_IN-Pad9)") (class "Default")
      (node (ref "U4") (pin "9") (pinfunction "PA16/A1_1/FCC_IN_9") (pintype "passive+no_connect"))
    )
    (net (code "109") (name "unconnected-(U4-PA17{slash}A1_2-Pad10)") (class "Default")
      (node (ref "U4") (pin "10") (pinfunction "PA17/A1_2_10") (pintype "passive+no_connect"))
    )
    (net (code "110") (name "unconnected-(U4-PB4-Pad52)") (class "Default")
      (node (ref "U4") (pin "52") (pinfunction "PB4_52") (pintype "passive+no_connect"))
    )
    (net (code "111") (name "unconnected-(U4-PB5-Pad53)") (class "Default")
      (node (ref "U4") (pin "53") (pinfunction "PB5_53") (pintype "passive+no_connect"))
    )
    (net (code "112") (name "unconnected-(U4-PB8-Pad60)") (class "Default")
      (node (ref "U4") (pin "60") (pinfunction "PB8_60") (pintype "passive+no_connect"))
    )
    (net (code "113") (name "unconnected-(U4-PB9-Pad61)") (class "Default")
      (node (ref "U4") (pin "61") (pinfunction "PB9_61") (pintype "passive+no_connect"))
    )
    (net (code "114") (name "unconnected-(U4-PB10-Pad62)") (class "Default")
      (node (ref "U4") (pin "62") (pinfunction "PB10_62") (pintype "passive+no_connect"))
    )
  )
)
